# clocking.net
KiCad netlist of a schematic drawn in Altium Designer
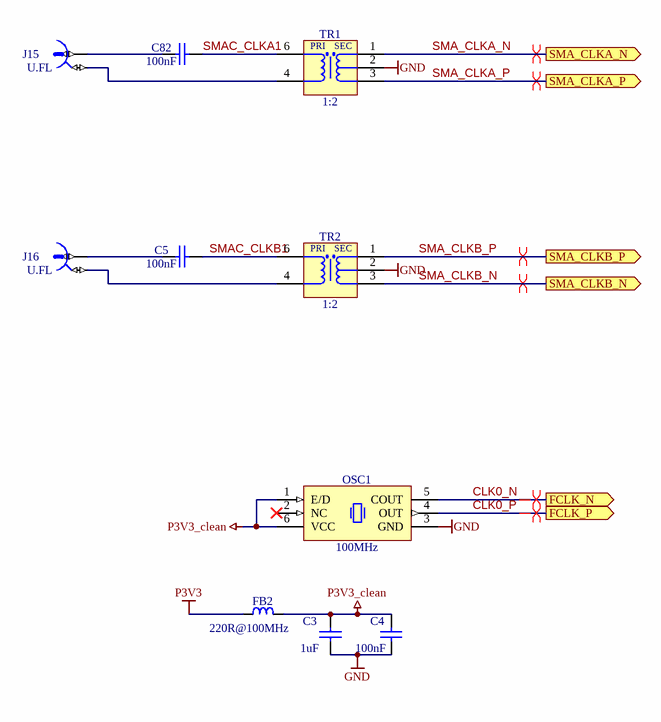
[diagram p0: clocking.SchDoc]

(export (version "E")
  (design (tool "Eeschema 10.0.6"))
  (components
    (comp (ref "C3")
      (value "1uF")
      (footprint "CAPC1608X87N")
      (description "Non-polarised capacitor")
      (fields
        (field (name "PART NUMBER") "CC0603_1UF_25V_10%_X7R")
        (field (name "VOLTAGE") "25V")
        (field (name "AUTHOR") "CERN DEM JLC")
      )
      (libsource (lib "Capacitors") (part "Capacitor - non polarized"))
    )
    (comp (ref "C4")
      (value "100nF")
      (footprint "CAPC1005X55N")
      (description "Non-polarised capacitor")
      (fields
        (field (name "PART NUMBER") "CC0402_100NF_16V_10%_X5R")
        (field (name "VOLTAGE") "16V")
        (field (name "AUTHOR") "CERN DEM JLC")
      )
      (libsource (lib "Capacitors") (part "Capacitor - non polarized"))
    )
    (comp (ref "C5")
      (value "100nF")
      (footprint "CAPC1005X55N")
      (description "Non-polarised capacitor")
      (fields
        (field (name "PART NUMBER") "CC0402_100NF_16V_10%_X5R")
        (field (name "VOLTAGE") "16V")
        (field (name "AUTHOR") "CERN DEM JLC")
      )
      (libsource (lib "Capacitors") (part "Capacitor - non polarized"))
    )
    (comp (ref "C82")
      (value "100nF")
      (footprint "CAPC1005X55N")
      (description "Non-polarised capacitor")
      (fields
        (field (name "PART NUMBER") "CC0402_100NF_16V_10%_X5R")
        (field (name "VOLTAGE") "16V")
        (field (name "AUTHOR") "CERN DEM JLC")
      )
      (libsource (lib "Capacitors") (part "Capacitor - non polarized"))
    )
    (comp (ref "FB2")
      (value "220R@100MHz")
      (footprint "INDC2012X105N")
      (description "Inductor")
      (fields
        (field (name "PART NUMBER") "IND0805_MURATA_BLM21PG221SN1D")
        (field (name "POWER") "2A")
        (field (name "AUTHOR") "CERN DEM JLC")
      )
      (libsource (lib "Inductors & Transformers") (part "Inductor"))
    )
    (comp (ref "J15")
      (value "U.FL")
      (footprint "HIROSE_U.FL-R-SMT-1(10)")
      (fields
        (field (name "PART NUMBER") "HIROSE_U.FL-R-SMT-1(10)")
        (field (name "MANUFACTURER") "HIROSE (HRS)")
        (field (name "MANUFACTURER PART NUMBER") "U.FL-R-SMT-1(10)")
        (field (name "AUTHOR") "CERN DEM JLC")
      )
      (libsource (lib "Connectors") (part "Coax_1Male_1Shield"))
    )
    (comp (ref "J16")
      (value "U.FL")
      (footprint "HIROSE_U.FL-R-SMT-1(10)")
      (fields
        (field (name "PART NUMBER") "HIROSE_U.FL-R-SMT-1(10)")
        (field (name "MANUFACTURER") "HIROSE (HRS)")
        (field (name "MANUFACTURER PART NUMBER") "U.FL-R-SMT-1(10)")
        (field (name "AUTHOR") "CERN DEM JLC")
      )
      (libsource (lib "Connectors") (part "Coax_1Male_1Shield"))
    )
    (comp (ref "OSC1")
      (value "100MHz")
      (footprint "OSC_CRYSTEK_CCLD-033")
      (description "3.3V, ± 50ppm, 0°C to +70°C, Surface Mount LVDS Clock Oscillator (CCLD-033 Series)")
      (fields
        (field (name "PART NUMBER") "OSC_100MHZ_CRYSTEK_CCLD-033-50-100.000")
        (field (name "MANUFACTURER") "CRYSTEK CRYSTAL")
        (field (name "AUTHOR") "CERN DEM JLC")
      )
      (libsource (lib "ICs And Semiconductors") (part "OSC_CRYSTEK_CCLD-033"))
    )
    (comp (ref "TR1")
      (value "1:2")
      (footprint "XFMR_MINI-CIRCUITS_AT1521")
      (description "50 Ohms 10 to 700 MHzz RF Transformer")
      (fields
        (field (name "MANUFACTURER") "MINI-CIRCUITS")
        (field (name "MANUFACTURER PART NUMBER") "TC2-72T+")
        (field (name "AUTHOR") "GK")
      )
      (libsource (lib "Inductors_Transformers") (part "XFMR_MINI-CIRCUITS_TC2-72T+"))
    )
    (comp (ref "TR2")
      (value "1:2")
      (footprint "XFMR_MINI-CIRCUITS_AT1521")
      (description "50 Ohms 10 to 700 MHzz RF Transformer")
      (fields
        (field (name "MANUFACTURER") "MINI-CIRCUITS")
        (field (name "MANUFACTURER PART NUMBER") "TC2-72T+")
        (field (name "AUTHOR") "GK")
      )
      (libsource (lib "Inductors_Transformers") (part "XFMR_MINI-CIRCUITS_TC2-72T+"))
    )
  )
  (nets
    (net (code "1") (name "/CLK0_N") (class "Default")
      (node (ref "OSC1") (pin "5") (pinfunction "COUT_5") (pintype "passive"))
    )
    (net (code "2") (name "/CLK0_P") (class "Default")
      (node (ref "OSC1") (pin "4") (pinfunction "OUT_4") (pintype "output"))
    )
    (net (code "3") (name "/SMAC_CLKA1") (class "Default")
      (node (ref "C82") (pin "1") (pinfunction "1_1") (pintype "passive"))
      (node (ref "TR1") (pin "6") (pinfunction "PDOT_6") (pintype "passive"))
    )
    (net (code "4") (name "/SMAC_CLKB1") (class "Default")
      (node (ref "C5") (pin "1") (pinfunction "1_1") (pintype "passive"))
      (node (ref "TR2") (pin "6") (pinfunction "PDOT_6") (pintype "passive"))
    )
    (net (code "5") (name "/SMA_CLKA_N") (class "Default")
      (node (ref "TR1") (pin "1") (pinfunction "SDOT_1") (pintype "passive"))
    )
    (net (code "6") (name "/SMA_CLKA_P") (class "Default")
      (node (ref "TR1") (pin "3") (pinfunction "S_3") (pintype "passive"))
    )
    (net (code "7") (name "/SMA_CLKB_N") (class "Default")
      (node (ref "TR2") (pin "3") (pinfunction "S_3") (pintype "passive"))
    )
    (net (code "8") (name "/SMA_CLKB_P") (class "Default")
      (node (ref "TR2") (pin "1") (pinfunction "SDOT_1") (pintype "passive"))
    )
    (net (code "9") (name "GND") (class "Default")
      (node (ref "C3") (pin "1") (pinfunction "1_1") (pintype "passive"))
      (node (ref "C4") (pin "1") (pinfunction "1_1") (pintype "passive"))
      (node (ref "OSC1") (pin "3") (pinfunction "GND_3") (pintype "power_in"))
      (node (ref "TR1") (pin "2") (pinfunction "NC_2") (pintype "passive"))
      (node (ref "TR2") (pin "2") (pinfunction "NC_2") (pintype "passive"))
    )
    (net (code "10") (name "Net-(C5-Pad2)") (class "Default")
      (node (ref "C5") (pin "2") (pinfunction "2_2") (pintype "passive"))
      (node (ref "J16") (pin "1") (pinfunction "1_1") (pintype "bidirectional"))
    )
    (net (code "11") (name "Net-(C82-Pad2)") (class "Default")
      (node (ref "C82") (pin "2") (pinfunction "2_2") (pintype "passive"))
      (node (ref "J15") (pin "1") (pinfunction "1_1") (pintype "bidirectional"))
    )
    (net (code "12") (name "Net-(TR1-P)") (class "Default")
      (node (ref "J15") (pin "2") (pinfunction "2_2") (pintype "bidirectional"))
      (node (ref "TR1") (pin "4") (pinfunction "P_4") (pintype "passive"))
    )
    (net (code "13") (name "Net-(TR2-P)") (class "Default")
      (node (ref "J16") (pin "2") (pinfunction "2_2") (pintype "bidirectional"))
      (node (ref "TR2") (pin "4") (pinfunction "P_4") (pintype "passive"))
    )
    (net (code "14") (name "P3V3") (class "Default")
      (node (ref "FB2") (pin "1") (pinfunction "1_1") (pintype "passive"))
    )
    (net (code "15") (name "P3V3_clean") (class "Default")
      (node (ref "C3") (pin "2") (pinfunction "2_2") (pintype "passive"))
      (node (ref "C4") (pin "2") (pinfunction "2_2") (pintype "passive"))
      (node (ref "FB2") (pin "2") (pinfunction "2_2") (pintype "passive"))
      (node (ref "OSC1") (pin "1") (pinfunction "E/D_1") (pintype "input"))
      (node (ref "OSC1") (pin "6") (pinfunction "VCC_6") (pintype "power_in"))
    )
    (net (code "16") (name "unconnected-(OSC1-NC-Pad2)") (class "Default")
      (node (ref "OSC1") (pin "2") (pinfunction "NC_2") (pintype "input+no_connect"))
    )
  )
)
